# 03_PUSHBUTTON.net
KiCad netlist of a schematic drawn in Altium Designer
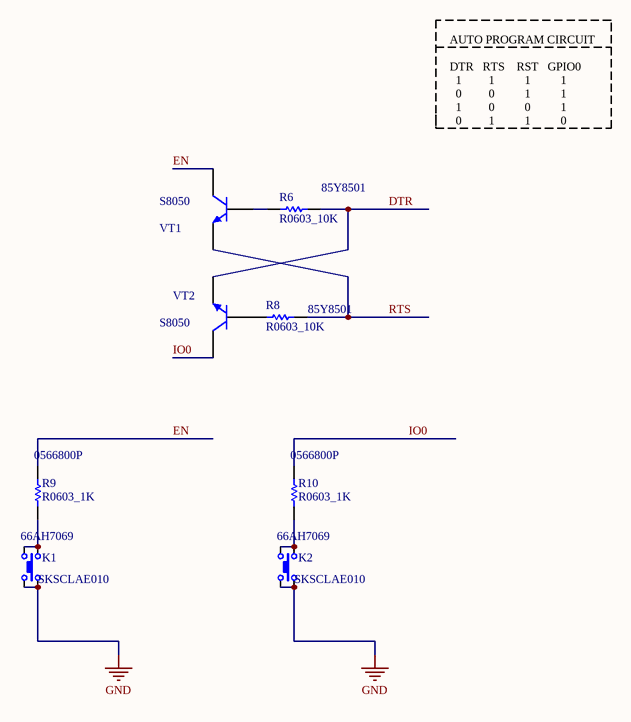
[diagram p0: 03_PUSHBUTTON.SchDoc]

(export (version "E")
  (design (tool "Eeschema 10.0.6"))
  (components
    (comp (ref "K1")
      (value "SKSCLAE010")
      (footprint "ButtonTACT_3.5*3.55_90")
      (description "Black Button Tactile Switch, Single Pole Single Throw (SPST) 50 mA 0.65mm Surface Mount")
      (fields
        (field (name "SUPPLIER PART NUMBER 1") "66AH7069")
        (field (name "MANUFACTURER") "Alps Electric")
      )
      (libsource (lib "RBS_library") (part "ButtonTACT"))
    )
    (comp (ref "K2")
      (value "SKSCLAE010")
      (footprint "ButtonTACT_3.5*3.55_90")
      (description "Black Button Tactile Switch, Single Pole Single Throw (SPST) 50 mA 0.65mm Surface Mount")
      (fields
        (field (name "SUPPLIER PART NUMBER 1") "66AH7069")
        (field (name "MANUFACTURER") "Alps Electric")
      )
      (libsource (lib "RBS_library") (part "ButtonTACT"))
    )
    (comp (ref "R6")
      (value "R0603_10K")
      (footprint "RESC1609X55X30LL15T15")
      (description "PANASONIC - ERJ-3EKF1002V. - THICK FILM CHIP RES, 0603, 1%, PRECISION")
      (fields
        (field (name "SUPPLIER PART NUMBER 1") "85Y8501")
        (field (name "MANUFACTURER") "Panasonic")
        (field (name "MANUFACTURER PART NUMBER") "ERJ-3EKF1002V")
      )
      (libsource (lib "RBS_library") (part "R0603"))
    )
    (comp (ref "R8")
      (value "R0603_10K")
      (footprint "RESC1609X55X30LL15T15")
      (description "PANASONIC - ERJ-3EKF1002V. - THICK FILM CHIP RES, 0603, 1%, PRECISION")
      (fields
        (field (name "SUPPLIER PART NUMBER 1") "85Y8501")
        (field (name "MANUFACTURER") "Panasonic")
        (field (name "MANUFACTURER PART NUMBER") "ERJ-3EKF1002V")
      )
      (libsource (lib "RBS_library") (part "R0603"))
    )
    (comp (ref "R9")
      (value "R0603_1K")
      (footprint "RESC1609X55X30LL15T15")
      (description "Res Thin Film 0603 1K Ohm 0.1% 1/10W ±25ppm/°C Molded SMD SMD Punched Carrier T/R")
      (fields
        (field (name "SUPPLIER PART NUMBER 1") "0566800P")
        (field (name "MANUFACTURER") "Panasonic")
        (field (name "MANUFACTURER PART NUMBER") "ERA-3AEB102V")
      )
      (libsource (lib "RBS_library") (part "R0603"))
    )
    (comp (ref "R10")
      (value "R0603_1K")
      (footprint "RESC1609X55X30LL15T15")
      (description "Res Thin Film 0603 1K Ohm 0.1% 1/10W ±25ppm/°C Molded SMD SMD Punched Carrier T/R")
      (fields
        (field (name "SUPPLIER PART NUMBER 1") "0566800P")
        (field (name "MANUFACTURER") "Panasonic")
        (field (name "MANUFACTURER PART NUMBER") "ERA-3AEB102V")
      )
      (libsource (lib "RBS_library") (part "R0603"))
    )
    (comp (ref "VT1")
      (value "S8050")
      (footprint "SMT_TRIODE_NPN")
      (description "Surface mount NPN transistor, package SOT-23")
      (libsource (lib "RBS_library") (part "SMT_TRIODE_NPN"))
    )
    (comp (ref "VT2")
      (value "S8050")
      (footprint "SMT_TRIODE_NPN")
      (description "Surface mount NPN transistor, package SOT-23")
      (libsource (lib "RBS_library") (part "SMT_TRIODE_NPN"))
    )
  )
  (nets
    (net (code "1") (name "/DTR") (class "Default")
      (node (ref "R6") (pin "2") (pinfunction "2_2") (pintype "passive"))
      (node (ref "VT2") (pin "2") (pinfunction "E_2") (pintype "passive"))
    )
    (net (code "2") (name "/EN") (class "Default")
      (node (ref "R9") (pin "2") (pinfunction "2_2") (pintype "passive"))
      (node (ref "VT1") (pin "3") (pinfunction "C_3") (pintype "passive"))
    )
    (net (code "3") (name "/IO0") (class "Default")
      (node (ref "R10") (pin "2") (pinfunction "2_2") (pintype "passive"))
      (node (ref "VT2") (pin "3") (pinfunction "C_3") (pintype "passive"))
    )
    (net (code "4") (name "/RTS") (class "Default")
      (node (ref "R8") (pin "2") (pinfunction "2_2") (pintype "passive"))
      (node (ref "VT1") (pin "2") (pinfunction "E_2") (pintype "passive"))
    )
    (net (code "5") (name "GND") (class "Default")
      (node (ref "K1") (pin "1") (pinfunction "1_1") (pintype "passive"))
      (node (ref "K1") (pin "3") (pinfunction "3_3") (pintype "passive"))
      (node (ref "K2") (pin "1") (pinfunction "1_1") (pintype "passive"))
      (node (ref "K2") (pin "3") (pinfunction "3_3") (pintype "passive"))
    )
    (net (code "6") (name "Net-(K1-Pad2)") (class "Default")
      (node (ref "K1") (pin "2") (pinfunction "2_2") (pintype "passive"))
      (node (ref "K1") (pin "4") (pinfunction "4_4") (pintype "passive"))
      (node (ref "R9") (pin "1") (pinfunction "1_1") (pintype "passive"))
    )
    (net (code "7") (name "Net-(K2-Pad2)") (class "Default")
      (node (ref "K2") (pin "2") (pinfunction "2_2") (pintype "passive"))
      (node (ref "K2") (pin "4") (pinfunction "4_4") (pintype "passive"))
      (node (ref "R10") (pin "1") (pinfunction "1_1") (pintype "passive"))
    )
    (net (code "8") (name "Net-(VT1-B)") (class "Default")
      (node (ref "R6") (pin "1") (pinfunction "1_1") (pintype "passive"))
      (node (ref "VT1") (pin "1") (pinfunction "B_1") (pintype "passive"))
    )
    (net (code "9") (name "Net-(VT2-B)") (class "Default")
      (node (ref "R8") (pin "1") (pinfunction "1_1") (pintype "passive"))
      (node (ref "VT2") (pin "1") (pinfunction "B_1") (pintype "passive"))
    )
  )
)
